# analog-io-breakout.net
KiCad netlist of a schematic drawn in EAGLE
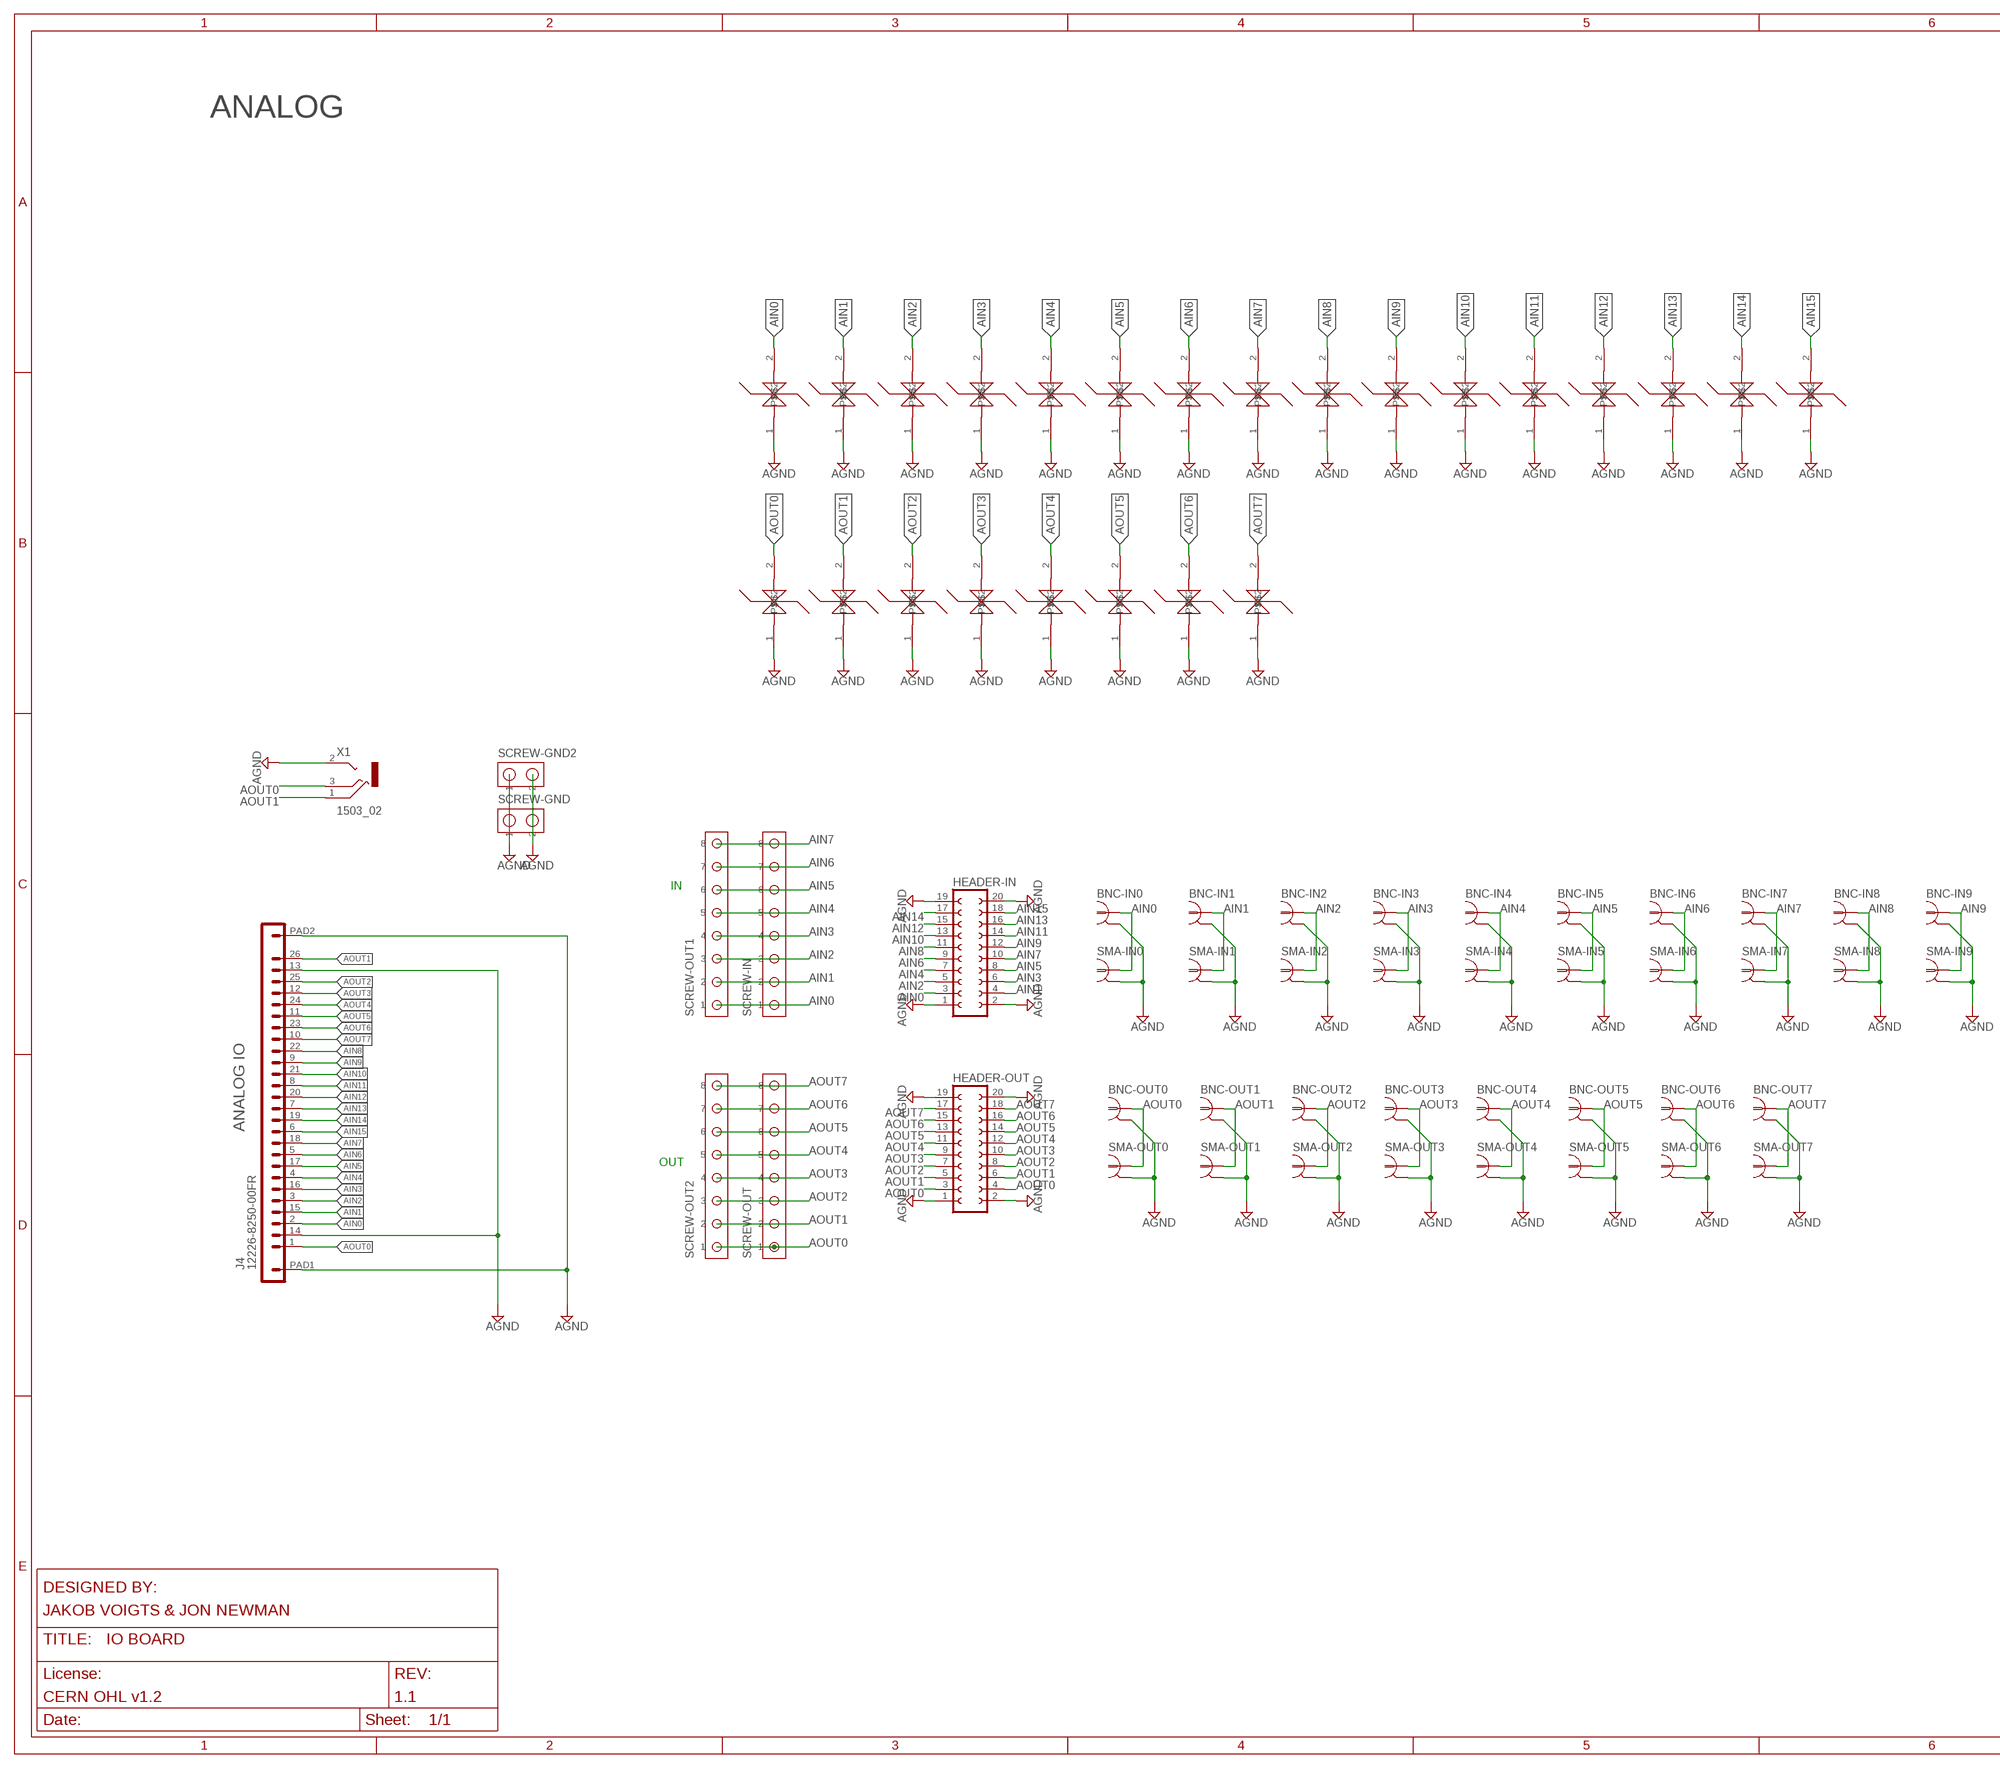
[diagram p0: schematic, sheet 1, part 1 of 2]
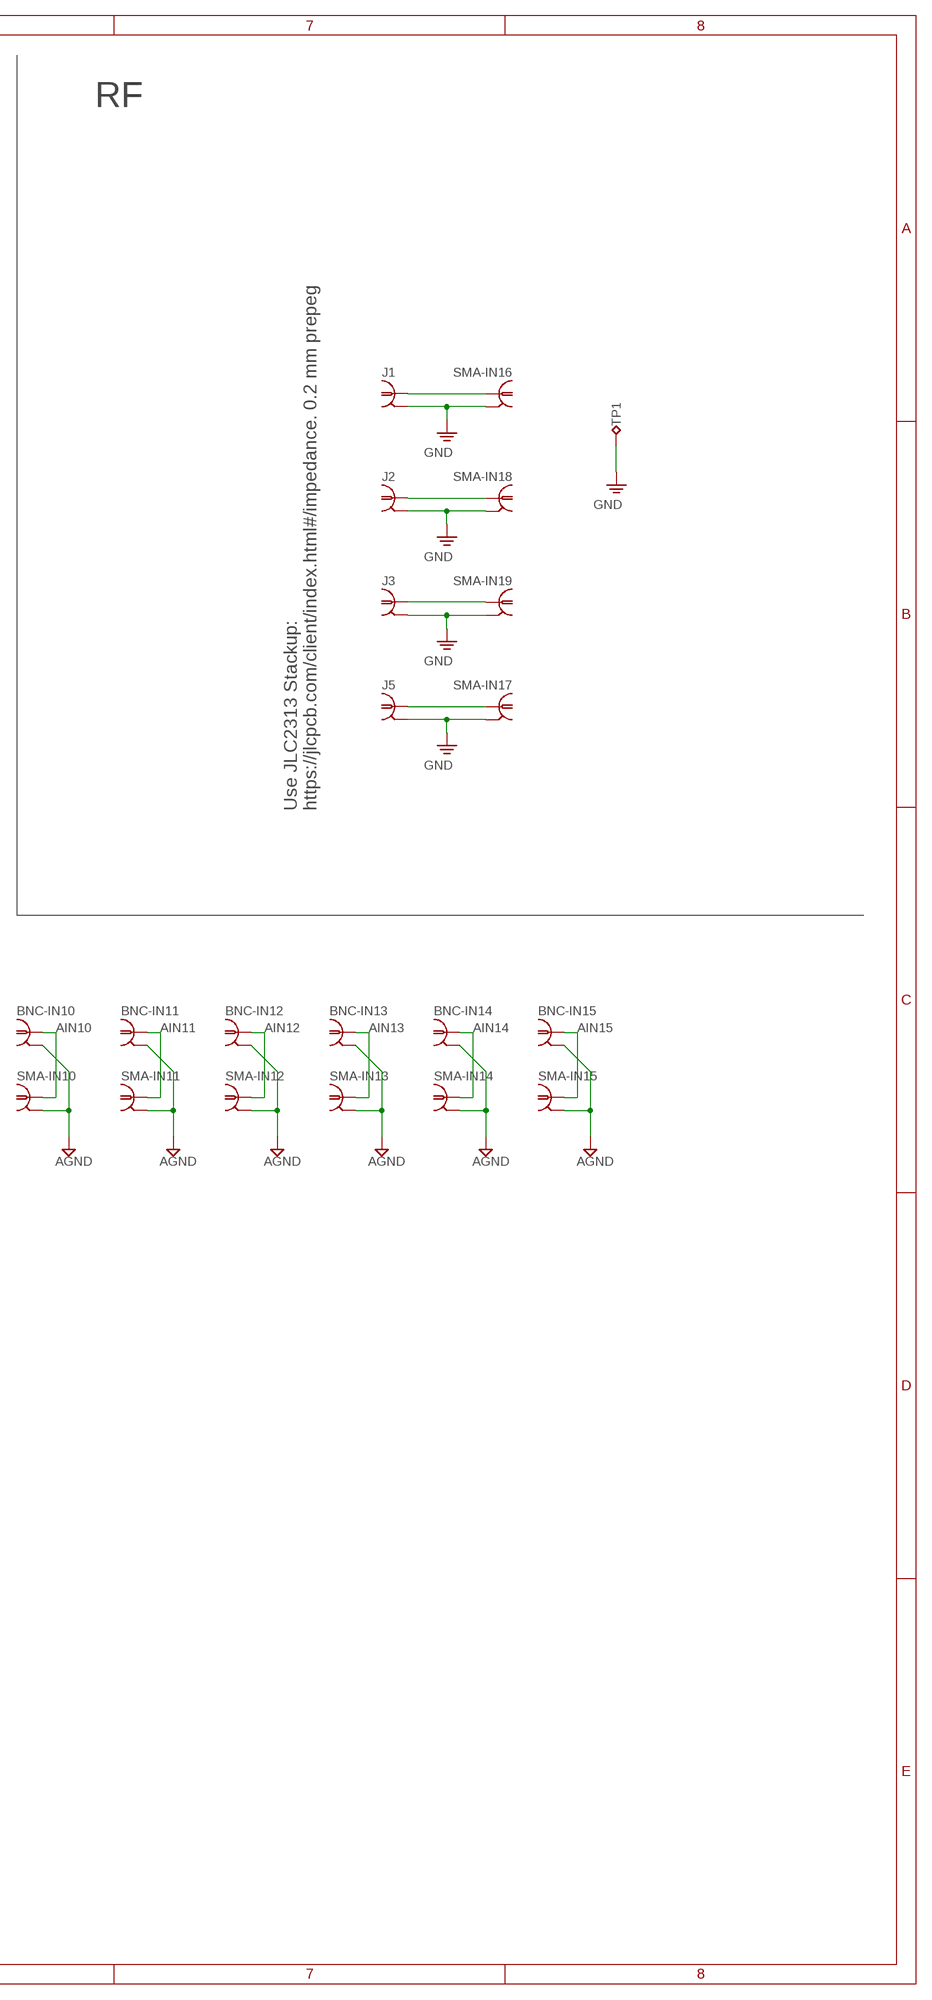
[diagram p1: schematic, sheet 1, part 2 of 2]

(export (version "E")
  (design (tool "Eeschema 10.0.6"))
  (components
    (comp (ref "BNC-IN0")
      (value "COAX_B35N61-LARGE-HOLES")
      (footprint "eagle-import:B35N61_LARGE-HOLES")
      (libsource (lib "eagle-import") (part "COAX_B35N61-LARGE-HOLES"))
    )
    (comp (ref "BNC-IN1")
      (value "COAX_B35N61-LARGE-HOLES")
      (footprint "eagle-import:B35N61_LARGE-HOLES")
      (libsource (lib "eagle-import") (part "COAX_B35N61-LARGE-HOLES"))
    )
    (comp (ref "BNC-IN2")
      (value "COAX_B35N61-LARGE-HOLES")
      (footprint "eagle-import:B35N61_LARGE-HOLES")
      (libsource (lib "eagle-import") (part "COAX_B35N61-LARGE-HOLES"))
    )
    (comp (ref "BNC-IN3")
      (value "COAX_B35N61-LARGE-HOLES")
      (footprint "eagle-import:B35N61_LARGE-HOLES")
      (libsource (lib "eagle-import") (part "COAX_B35N61-LARGE-HOLES"))
    )
    (comp (ref "BNC-IN4")
      (value "COAX_B35N61-LARGE-HOLES")
      (footprint "eagle-import:B35N61_LARGE-HOLES")
      (libsource (lib "eagle-import") (part "COAX_B35N61-LARGE-HOLES"))
    )
    (comp (ref "BNC-IN5")
      (value "COAX_B35N61-LARGE-HOLES")
      (footprint "eagle-import:B35N61_LARGE-HOLES")
      (libsource (lib "eagle-import") (part "COAX_B35N61-LARGE-HOLES"))
    )
    (comp (ref "BNC-IN6")
      (value "COAX_B35N61-LARGE-HOLES")
      (footprint "eagle-import:B35N61_LARGE-HOLES")
      (libsource (lib "eagle-import") (part "COAX_B35N61-LARGE-HOLES"))
    )
    (comp (ref "BNC-IN7")
      (value "COAX_B35N61-LARGE-HOLES")
      (footprint "eagle-import:B35N61_LARGE-HOLES")
      (libsource (lib "eagle-import") (part "COAX_B35N61-LARGE-HOLES"))
    )
    (comp (ref "BNC-IN8")
      (value "COAX_B35N61-LARGE-HOLES")
      (footprint "eagle-import:B35N61_LARGE-HOLES")
      (libsource (lib "eagle-import") (part "COAX_B35N61-LARGE-HOLES"))
    )
    (comp (ref "BNC-IN9")
      (value "COAX_B35N61-LARGE-HOLES")
      (footprint "eagle-import:B35N61_LARGE-HOLES")
      (libsource (lib "eagle-import") (part "COAX_B35N61-LARGE-HOLES"))
    )
    (comp (ref "BNC-IN10")
      (value "COAX_B35N61-LARGE-HOLES")
      (footprint "eagle-import:B35N61_LARGE-HOLES")
      (libsource (lib "eagle-import") (part "COAX_B35N61-LARGE-HOLES"))
    )
    (comp (ref "BNC-IN11")
      (value "COAX_B35N61-LARGE-HOLES")
      (footprint "eagle-import:B35N61_LARGE-HOLES")
      (libsource (lib "eagle-import") (part "COAX_B35N61-LARGE-HOLES"))
    )
    (comp (ref "BNC-IN12")
      (value "COAX_B35N61-LARGE-HOLES")
      (footprint "eagle-import:B35N61_LARGE-HOLES")
      (libsource (lib "eagle-import") (part "COAX_B35N61-LARGE-HOLES"))
    )
    (comp (ref "BNC-IN13")
      (value "COAX_B35N61-LARGE-HOLES")
      (footprint "eagle-import:B35N61_LARGE-HOLES")
      (libsource (lib "eagle-import") (part "COAX_B35N61-LARGE-HOLES"))
    )
    (comp (ref "BNC-IN14")
      (value "COAX_B35N61-LARGE-HOLES")
      (footprint "eagle-import:B35N61_LARGE-HOLES")
      (libsource (lib "eagle-import") (part "COAX_B35N61-LARGE-HOLES"))
    )
    (comp (ref "BNC-IN15")
      (value "COAX_B35N61-LARGE-HOLES")
      (footprint "eagle-import:B35N61_LARGE-HOLES")
      (libsource (lib "eagle-import") (part "COAX_B35N61-LARGE-HOLES"))
    )
    (comp (ref "BNC-OUT0")
      (value "COAX_B35N61-LARGE-HOLES")
      (footprint "eagle-import:B35N61_LARGE-HOLES")
      (libsource (lib "eagle-import") (part "COAX_B35N61-LARGE-HOLES"))
    )
    (comp (ref "BNC-OUT1")
      (value "COAX_B35N61-LARGE-HOLES")
      (footprint "eagle-import:B35N61_LARGE-HOLES")
      (libsource (lib "eagle-import") (part "COAX_B35N61-LARGE-HOLES"))
    )
    (comp (ref "BNC-OUT2")
      (value "COAX_B35N61-LARGE-HOLES")
      (footprint "eagle-import:B35N61_LARGE-HOLES")
      (libsource (lib "eagle-import") (part "COAX_B35N61-LARGE-HOLES"))
    )
    (comp (ref "BNC-OUT3")
      (value "COAX_B35N61-LARGE-HOLES")
      (footprint "eagle-import:B35N61_LARGE-HOLES")
      (libsource (lib "eagle-import") (part "COAX_B35N61-LARGE-HOLES"))
    )
    (comp (ref "BNC-OUT4")
      (value "COAX_B35N61-LARGE-HOLES")
      (footprint "eagle-import:B35N61_LARGE-HOLES")
      (libsource (lib "eagle-import") (part "COAX_B35N61-LARGE-HOLES"))
    )
    (comp (ref "BNC-OUT5")
      (value "COAX_B35N61-LARGE-HOLES")
      (footprint "eagle-import:B35N61_LARGE-HOLES")
      (libsource (lib "eagle-import") (part "COAX_B35N61-LARGE-HOLES"))
    )
    (comp (ref "BNC-OUT6")
      (value "COAX_B35N61-LARGE-HOLES")
      (footprint "eagle-import:B35N61_LARGE-HOLES")
      (libsource (lib "eagle-import") (part "COAX_B35N61-LARGE-HOLES"))
    )
    (comp (ref "BNC-OUT7")
      (value "COAX_B35N61-LARGE-HOLES")
      (footprint "eagle-import:B35N61_LARGE-HOLES")
      (libsource (lib "eagle-import") (part "COAX_B35N61-LARGE-HOLES"))
    )
    (comp (ref "HEADER-IN")
      (value "FE10-2")
      (footprint "eagle-import:FE10-2")
      (libsource (lib "eagle-import") (part "FE10-2"))
    )
    (comp (ref "HEADER-OUT")
      (value "FE10-2")
      (footprint "eagle-import:FE10-2")
      (libsource (lib "eagle-import") (part "FE10-2"))
    )
    (comp (ref "J1")
      (value "COAX_MMCX-RA")
      (footprint "eagle-import:MMCX-J-P-X-RA-SM1")
      (libsource (lib "eagle-import") (part "COAX_MMCX-RA"))
    )
    (comp (ref "J2")
      (value "COAX_MMCX-RA")
      (footprint "eagle-import:MMCX-J-P-X-RA-SM1")
      (libsource (lib "eagle-import") (part "COAX_MMCX-RA"))
    )
    (comp (ref "J3")
      (value "COAX_MMCX-RA")
      (footprint "eagle-import:MMCX-J-P-X-RA-SM1")
      (libsource (lib "eagle-import") (part "COAX_MMCX-RA"))
    )
    (comp (ref "J4")
      (value "12226-8250-00FR")
      (footprint "eagle-import:12226-82X0-00XX")
      (libsource (lib "eagle-import") (part "PINHD-1X26_122"))
    )
    (comp (ref "J5")
      (value "COAX_MMCX-RA")
      (footprint "eagle-import:MMCX-J-P-X-RA-SM1")
      (libsource (lib "eagle-import") (part "COAX_MMCX-RA"))
    )
    (comp (ref "SCREW-GND")
      (value "SCREW2")
      (footprint "eagle-import:SCREW2")
      (libsource (lib "eagle-import") (part "SCREW2"))
    )
    (comp (ref "SCREW-GND2")
      (value "SCREW2")
      (footprint "eagle-import:SCREW2")
      (libsource (lib "eagle-import") (part "SCREW2"))
    )
    (comp (ref "SCREW-IN")
      (value "SCREW8")
      (footprint "eagle-import:SCREW8")
      (libsource (lib "eagle-import") (part "SCREW8"))
    )
    (comp (ref "SCREW-OUT")
      (value "SCREW8")
      (footprint "eagle-import:SCREW8")
      (libsource (lib "eagle-import") (part "SCREW8"))
    )
    (comp (ref "SCREW-OUT1")
      (value "SCREW8")
      (footprint "eagle-import:SCREW8")
      (libsource (lib "eagle-import") (part "SCREW8"))
    )
    (comp (ref "SCREW-OUT2")
      (value "SCREW8")
      (footprint "eagle-import:SCREW8")
      (libsource (lib "eagle-import") (part "SCREW8"))
    )
    (comp (ref "SMA-IN0")
      (value "COAX_SMA-VERT")
      (footprint "eagle-import:SMA_JACK_142-0701-201")
      (libsource (lib "eagle-import") (part "COAX_SMA-VERT"))
    )
    (comp (ref "SMA-IN1")
      (value "COAX_SMA-VERT")
      (footprint "eagle-import:SMA_JACK_142-0701-201")
      (libsource (lib "eagle-import") (part "COAX_SMA-VERT"))
    )
    (comp (ref "SMA-IN2")
      (value "COAX_SMA-VERT")
      (footprint "eagle-import:SMA_JACK_142-0701-201")
      (libsource (lib "eagle-import") (part "COAX_SMA-VERT"))
    )
    (comp (ref "SMA-IN3")
      (value "COAX_SMA-VERT")
      (footprint "eagle-import:SMA_JACK_142-0701-201")
      (libsource (lib "eagle-import") (part "COAX_SMA-VERT"))
    )
    (comp (ref "SMA-IN4")
      (value "COAX_SMA-VERT")
      (footprint "eagle-import:SMA_JACK_142-0701-201")
      (libsource (lib "eagle-import") (part "COAX_SMA-VERT"))
    )
    (comp (ref "SMA-IN5")
      (value "COAX_SMA-VERT")
      (footprint "eagle-import:SMA_JACK_142-0701-201")
      (libsource (lib "eagle-import") (part "COAX_SMA-VERT"))
    )
    (comp (ref "SMA-IN6")
      (value "COAX_SMA-VERT")
      (footprint "eagle-import:SMA_JACK_142-0701-201")
      (libsource (lib "eagle-import") (part "COAX_SMA-VERT"))
    )
    (comp (ref "SMA-IN7")
      (value "COAX_SMA-VERT")
      (footprint "eagle-import:SMA_JACK_142-0701-201")
      (libsource (lib "eagle-import") (part "COAX_SMA-VERT"))
    )
    (comp (ref "SMA-IN8")
      (value "COAX_SMA-VERT")
      (footprint "eagle-import:SMA_JACK_142-0701-201")
      (libsource (lib "eagle-import") (part "COAX_SMA-VERT"))
    )
    (comp (ref "SMA-IN9")
      (value "COAX_SMA-VERT")
      (footprint "eagle-import:SMA_JACK_142-0701-201")
      (libsource (lib "eagle-import") (part "COAX_SMA-VERT"))
    )
    (comp (ref "SMA-IN10")
      (value "COAX_SMA-VERT")
      (footprint "eagle-import:SMA_JACK_142-0701-201")
      (libsource (lib "eagle-import") (part "COAX_SMA-VERT"))
    )
    (comp (ref "SMA-IN11")
      (value "COAX_SMA-VERT")
      (footprint "eagle-import:SMA_JACK_142-0701-201")
      (libsource (lib "eagle-import") (part "COAX_SMA-VERT"))
    )
    (comp (ref "SMA-IN12")
      (value "COAX_SMA-VERT")
      (footprint "eagle-import:SMA_JACK_142-0701-201")
      (libsource (lib "eagle-import") (part "COAX_SMA-VERT"))
    )
    (comp (ref "SMA-IN13")
      (value "COAX_SMA-VERT")
      (footprint "eagle-import:SMA_JACK_142-0701-201")
      (libsource (lib "eagle-import") (part "COAX_SMA-VERT"))
    )
    (comp (ref "SMA-IN14")
      (value "COAX_SMA-VERT")
      (footprint "eagle-import:SMA_JACK_142-0701-201")
      (libsource (lib "eagle-import") (part "COAX_SMA-VERT"))
    )
    (comp (ref "SMA-IN15")
      (value "COAX_SMA-VERT")
      (footprint "eagle-import:SMA_JACK_142-0701-201")
      (libsource (lib "eagle-import") (part "COAX_SMA-VERT"))
    )
    (comp (ref "SMA-IN16")
      (value "COAX_SMA-VERT")
      (footprint "eagle-import:SMA_JACK_142-0701-201")
      (libsource (lib "eagle-import") (part "COAX_SMA-VERT"))
    )
    (comp (ref "SMA-IN17")
      (value "COAX_SMA-VERT")
      (footprint "eagle-import:SMA_JACK_142-0701-201")
      (libsource (lib "eagle-import") (part "COAX_SMA-VERT"))
    )
    (comp (ref "SMA-IN18")
      (value "COAX_SMA-VERT")
      (footprint "eagle-import:SMA_JACK_142-0701-201")
      (libsource (lib "eagle-import") (part "COAX_SMA-VERT"))
    )
    (comp (ref "SMA-IN19")
      (value "COAX_SMA-VERT")
      (footprint "eagle-import:SMA_JACK_142-0701-201")
      (libsource (lib "eagle-import") (part "COAX_SMA-VERT"))
    )
    (comp (ref "SMA-OUT0")
      (value "COAX_SMA-VERT")
      (footprint "eagle-import:SMA_JACK_142-0701-201")
      (libsource (lib "eagle-import") (part "COAX_SMA-VERT"))
    )
    (comp (ref "SMA-OUT1")
      (value "COAX_SMA-VERT")
      (footprint "eagle-import:SMA_JACK_142-0701-201")
      (libsource (lib "eagle-import") (part "COAX_SMA-VERT"))
    )
    (comp (ref "SMA-OUT2")
      (value "COAX_SMA-VERT")
      (footprint "eagle-import:SMA_JACK_142-0701-201")
      (libsource (lib "eagle-import") (part "COAX_SMA-VERT"))
    )
    (comp (ref "SMA-OUT3")
      (value "COAX_SMA-VERT")
      (footprint "eagle-import:SMA_JACK_142-0701-201")
      (libsource (lib "eagle-import") (part "COAX_SMA-VERT"))
    )
    (comp (ref "SMA-OUT4")
      (value "COAX_SMA-VERT")
      (footprint "eagle-import:SMA_JACK_142-0701-201")
      (libsource (lib "eagle-import") (part "COAX_SMA-VERT"))
    )
    (comp (ref "SMA-OUT5")
      (value "COAX_SMA-VERT")
      (footprint "eagle-import:SMA_JACK_142-0701-201")
      (libsource (lib "eagle-import") (part "COAX_SMA-VERT"))
    )
    (comp (ref "SMA-OUT6")
      (value "COAX_SMA-VERT")
      (footprint "eagle-import:SMA_JACK_142-0701-201")
      (libsource (lib "eagle-import") (part "COAX_SMA-VERT"))
    )
    (comp (ref "SMA-OUT7")
      (value "COAX_SMA-VERT")
      (footprint "eagle-import:SMA_JACK_142-0701-201")
      (libsource (lib "eagle-import") (part "COAX_SMA-VERT"))
    )
    (comp (ref "TP1")
      (value "TP_2MM")
      (footprint "eagle-import:TESTPOINT_2MM")
      (libsource (lib "eagle-import") (part "TP_2MM"))
    )
    (comp (ref "U$1")
      (value "DIODE-ESD-BIDIRECTIONALDO-214AA")
      (footprint "eagle-import:DIOC7026X260")
      (libsource (lib "eagle-import") (part "DIODE-ESD-BIDIRECTIONALDO-214AA"))
    )
    (comp (ref "U$2")
      (value "DIODE-ESD-BIDIRECTIONALDO-214AA")
      (footprint "eagle-import:DIOC7026X260")
      (libsource (lib "eagle-import") (part "DIODE-ESD-BIDIRECTIONALDO-214AA"))
    )
    (comp (ref "U$3")
      (value "DIODE-ESD-BIDIRECTIONALDO-214AA")
      (footprint "eagle-import:DIOC7026X260")
      (libsource (lib "eagle-import") (part "DIODE-ESD-BIDIRECTIONALDO-214AA"))
    )
    (comp (ref "U$4")
      (value "DIODE-ESD-BIDIRECTIONALDO-214AA")
      (footprint "eagle-import:DIOC7026X260")
      (libsource (lib "eagle-import") (part "DIODE-ESD-BIDIRECTIONALDO-214AA"))
    )
    (comp (ref "U$5")
      (value "DIODE-ESD-BIDIRECTIONALDO-214AA")
      (footprint "eagle-import:DIOC7026X260")
      (libsource (lib "eagle-import") (part "DIODE-ESD-BIDIRECTIONALDO-214AA"))
    )
    (comp (ref "U$6")
      (value "DIODE-ESD-BIDIRECTIONALDO-214AA")
      (footprint "eagle-import:DIOC7026X260")
      (libsource (lib "eagle-import") (part "DIODE-ESD-BIDIRECTIONALDO-214AA"))
    )
    (comp (ref "U$7")
      (value "DIODE-ESD-BIDIRECTIONALDO-214AA")
      (footprint "eagle-import:DIOC7026X260")
      (libsource (lib "eagle-import") (part "DIODE-ESD-BIDIRECTIONALDO-214AA"))
    )
    (comp (ref "U$8")
      (value "DIODE-ESD-BIDIRECTIONALDO-214AA")
      (footprint "eagle-import:DIOC7026X260")
      (libsource (lib "eagle-import") (part "DIODE-ESD-BIDIRECTIONALDO-214AA"))
    )
    (comp (ref "U$9")
      (value "DIODE-ESD-BIDIRECTIONALDO-214AA")
      (footprint "eagle-import:DIOC7026X260")
      (libsource (lib "eagle-import") (part "DIODE-ESD-BIDIRECTIONALDO-214AA"))
    )
    (comp (ref "U$10")
      (value "DIODE-ESD-BIDIRECTIONALDO-214AA")
      (footprint "eagle-import:DIOC7026X260")
      (libsource (lib "eagle-import") (part "DIODE-ESD-BIDIRECTIONALDO-214AA"))
    )
    (comp (ref "U$11")
      (value "DIODE-ESD-BIDIRECTIONALDO-214AA")
      (footprint "eagle-import:DIOC7026X260")
      (libsource (lib "eagle-import") (part "DIODE-ESD-BIDIRECTIONALDO-214AA"))
    )
    (comp (ref "U$12")
      (value "DIODE-ESD-BIDIRECTIONALDO-214AA")
      (footprint "eagle-import:DIOC7026X260")
      (libsource (lib "eagle-import") (part "DIODE-ESD-BIDIRECTIONALDO-214AA"))
    )
    (comp (ref "U$13")
      (value "DIODE-ESD-BIDIRECTIONALDO-214AA")
      (footprint "eagle-import:DIOC7026X260")
      (libsource (lib "eagle-import") (part "DIODE-ESD-BIDIRECTIONALDO-214AA"))
    )
    (comp (ref "U$14")
      (value "DIODE-ESD-BIDIRECTIONALDO-214AA")
      (footprint "eagle-import:DIOC7026X260")
      (libsource (lib "eagle-import") (part "DIODE-ESD-BIDIRECTIONALDO-214AA"))
    )
    (comp (ref "U$15")
      (value "DIODE-ESD-BIDIRECTIONALDO-214AA")
      (footprint "eagle-import:DIOC7026X260")
      (libsource (lib "eagle-import") (part "DIODE-ESD-BIDIRECTIONALDO-214AA"))
    )
    (comp (ref "U$16")
      (value "DIODE-ESD-BIDIRECTIONALDO-214AA")
      (footprint "eagle-import:DIOC7026X260")
      (libsource (lib "eagle-import") (part "DIODE-ESD-BIDIRECTIONALDO-214AA"))
    )
    (comp (ref "U$17")
      (value "DIODE-ESD-BIDIRECTIONALDO-214AA")
      (footprint "eagle-import:DIOC7026X260")
      (libsource (lib "eagle-import") (part "DIODE-ESD-BIDIRECTIONALDO-214AA"))
    )
    (comp (ref "U$18")
      (value "DIODE-ESD-BIDIRECTIONALDO-214AA")
      (footprint "eagle-import:DIOC7026X260")
      (libsource (lib "eagle-import") (part "DIODE-ESD-BIDIRECTIONALDO-214AA"))
    )
    (comp (ref "U$19")
      (value "DIODE-ESD-BIDIRECTIONALDO-214AA")
      (footprint "eagle-import:DIOC7026X260")
      (libsource (lib "eagle-import") (part "DIODE-ESD-BIDIRECTIONALDO-214AA"))
    )
    (comp (ref "U$20")
      (value "DIODE-ESD-BIDIRECTIONALDO-214AA")
      (footprint "eagle-import:DIOC7026X260")
      (libsource (lib "eagle-import") (part "DIODE-ESD-BIDIRECTIONALDO-214AA"))
    )
    (comp (ref "U$21")
      (value "DIODE-ESD-BIDIRECTIONALDO-214AA")
      (footprint "eagle-import:DIOC7026X260")
      (libsource (lib "eagle-import") (part "DIODE-ESD-BIDIRECTIONALDO-214AA"))
    )
    (comp (ref "U$22")
      (value "DIODE-ESD-BIDIRECTIONALDO-214AA")
      (footprint "eagle-import:DIOC7026X260")
      (libsource (lib "eagle-import") (part "DIODE-ESD-BIDIRECTIONALDO-214AA"))
    )
    (comp (ref "U$23")
      (value "DIODE-ESD-BIDIRECTIONALDO-214AA")
      (footprint "eagle-import:DIOC7026X260")
      (libsource (lib "eagle-import") (part "DIODE-ESD-BIDIRECTIONALDO-214AA"))
    )
    (comp (ref "U$24")
      (value "DIODE-ESD-BIDIRECTIONALDO-214AA")
      (footprint "eagle-import:DIOC7026X260")
      (libsource (lib "eagle-import") (part "DIODE-ESD-BIDIRECTIONALDO-214AA"))
    )
    (comp (ref "X1")
      (value "1503_02")
      (footprint "eagle-import:1503_02")
      (libsource (lib "eagle-import") (part "1503_02"))
    )
  )
  (nets
    (net (code "1") (name "AGND") (class "Default")
      (node (ref "BNC-IN0") (pin "2") (pinfunction "2_2") (pintype "passive"))
      (node (ref "BNC-IN0") (pin "3") (pinfunction "2_3") (pintype "passive"))
      (node (ref "BNC-IN0") (pin "4") (pinfunction "2_4") (pintype "passive"))
      (node (ref "BNC-IN0") (pin "5") (pinfunction "2_5") (pintype "passive"))
      (node (ref "BNC-IN1") (pin "2") (pinfunction "2_2") (pintype "passive"))
      (node (ref "BNC-IN1") (pin "3") (pinfunction "2_3") (pintype "passive"))
      (node (ref "BNC-IN1") (pin "4") (pinfunction "2_4") (pintype "passive"))
      (node (ref "BNC-IN1") (pin "5") (pinfunction "2_5") (pintype "passive"))
      (node (ref "BNC-IN10") (pin "2") (pinfunction "2_2") (pintype "passive"))
      (node (ref "BNC-IN10") (pin "3") (pinfunction "2_3") (pintype "passive"))
      (node (ref "BNC-IN10") (pin "4") (pinfunction "2_4") (pintype "passive"))
      (node (ref "BNC-IN10") (pin "5") (pinfunction "2_5") (pintype "passive"))
      (node (ref "BNC-IN11") (pin "2") (pinfunction "2_2") (pintype "passive"))
      (node (ref "BNC-IN11") (pin "3") (pinfunction "2_3") (pintype "passive"))
      (node (ref "BNC-IN11") (pin "4") (pinfunction "2_4") (pintype "passive"))
      (node (ref "BNC-IN11") (pin "5") (pinfunction "2_5") (pintype "passive"))
      (node (ref "BNC-IN12") (pin "2") (pinfunction "2_2") (pintype "passive"))
      (node (ref "BNC-IN12") (pin "3") (pinfunction "2_3") (pintype "passive"))
      (node (ref "BNC-IN12") (pin "4") (pinfunction "2_4") (pintype "passive"))
      (node (ref "BNC-IN12") (pin "5") (pinfunction "2_5") (pintype "passive"))
      (node (ref "BNC-IN13") (pin "2") (pinfunction "2_2") (pintype "passive"))
      (node (ref "BNC-IN13") (pin "3") (pinfunction "2_3") (pintype "passive"))
      (node (ref "BNC-IN13") (pin "4") (pinfunction "2_4") (pintype "passive"))
      (node (ref "BNC-IN13") (pin "5") (pinfunction "2_5") (pintype "passive"))
      (node (ref "BNC-IN14") (pin "2") (pinfunction "2_2") (pintype "passive"))
      (node (ref "BNC-IN14") (pin "3") (pinfunction "2_3") (pintype "passive"))
      (node (ref "BNC-IN14") (pin "4") (pinfunction "2_4") (pintype "passive"))
      (node (ref "BNC-IN14") (pin "5") (pinfunction "2_5") (pintype "passive"))
      (node (ref "BNC-IN15") (pin "2") (pinfunction "2_2") (pintype "passive"))
      (node (ref "BNC-IN15") (pin "3") (pinfunction "2_3") (pintype "passive"))
      (node (ref "BNC-IN15") (pin "4") (pinfunction "2_4") (pintype "passive"))
      (node (ref "BNC-IN15") (pin "5") (pinfunction "2_5") (pintype "passive"))
      (node (ref "BNC-IN2") (pin "2") (pinfunction "2_2") (pintype "passive"))
      (node (ref "BNC-IN2") (pin "3") (pinfunction "2_3") (pintype "passive"))
      (node (ref "BNC-IN2") (pin "4") (pinfunction "2_4") (pintype "passive"))
      (node (ref "BNC-IN2") (pin "5") (pinfunction "2_5") (pintype "passive"))
      (node (ref "BNC-IN3") (pin "2") (pinfunction "2_2") (pintype "passive"))
      (node (ref "BNC-IN3") (pin "3") (pinfunction "2_3") (pintype "passive"))
      (node (ref "BNC-IN3") (pin "4") (pinfunction "2_4") (pintype "passive"))
      (node (ref "BNC-IN3") (pin "5") (pinfunction "2_5") (pintype "passive"))
      (node (ref "BNC-IN4") (pin "2") (pinfunction "2_2") (pintype "passive"))
      (node (ref "BNC-IN4") (pin "3") (pinfunction "2_3") (pintype "passive"))
      (node (ref "BNC-IN4") (pin "4") (pinfunction "2_4") (pintype "passive"))
      (node (ref "BNC-IN4") (pin "5") (pinfunction "2_5") (pintype "passive"))
      (node (ref "BNC-IN5") (pin "2") (pinfunction "2_2") (pintype "passive"))
      (node (ref "BNC-IN5") (pin "3") (pinfunction "2_3") (pintype "passive"))
      (node (ref "BNC-IN5") (pin "4") (pinfunction "2_4") (pintype "passive"))
      (node (ref "BNC-IN5") (pin "5") (pinfunction "2_5") (pintype "passive"))
      (node (ref "BNC-IN6") (pin "2") (pinfunction "2_2") (pintype "passive"))
      (node (ref "BNC-IN6") (pin "3") (pinfunction "2_3") (pintype "passive"))
      (node (ref "BNC-IN6") (pin "4") (pinfunction "2_4") (pintype "passive"))
      (node (ref "BNC-IN6") (pin "5") (pinfunction "2_5") (pintype "passive"))
      (node (ref "BNC-IN7") (pin "2") (pinfunction "2_2") (pintype "passive"))
      (node (ref "BNC-IN7") (pin "3") (pinfunction "2_3") (pintype "passive"))
      (node (ref "BNC-IN7") (pin "4") (pinfunction "2_4") (pintype "passive"))
      (node (ref "BNC-IN7") (pin "5") (pinfunction "2_5") (pintype "passive"))
      (node (ref "BNC-IN8") (pin "2") (pinfunction "2_2") (pintype "passive"))
      (node (ref "BNC-IN8") (pin "3") (pinfunction "2_3") (pintype "passive"))
      (node (ref "BNC-IN8") (pin "4") (pinfunction "2_4") (pintype "passive"))
      (node (ref "BNC-IN8") (pin "5") (pinfunction "2_5") (pintype "passive"))
      (node (ref "BNC-IN9") (pin "2") (pinfunction "2_2") (pintype "passive"))
      (node (ref "BNC-IN9") (pin "3") (pinfunction "2_3") (pintype "passive"))
      (node (ref "BNC-IN9") (pin "4") (pinfunction "2_4") (pintype "passive"))
      (node (ref "BNC-IN9") (pin "5") (pinfunction "2_5") (pintype "passive"))
      (node (ref "BNC-OUT0") (pin "2") (pinfunction "2_2") (pintype "passive"))
      (node (ref "BNC-OUT0") (pin "3") (pinfunction "2_3") (pintype "passive"))
      (node (ref "BNC-OUT0") (pin "4") (pinfunction "2_4") (pintype "passive"))
      (node (ref "BNC-OUT0") (pin "5") (pinfunction "2_5") (pintype "passive"))
      (node (ref "BNC-OUT1") (pin "2") (pinfunction "2_2") (pintype "passive"))
      (node (ref "BNC-OUT1") (pin "3") (pinfunction "2_3") (pintype "passive"))
      (node (ref "BNC-OUT1") (pin "4") (pinfunction "2_4") (pintype "passive"))
      (node (ref "BNC-OUT1") (pin "5") (pinfunction "2_5") (pintype "passive"))
      (node (ref "BNC-OUT2") (pin "2") (pinfunction "2_2") (pintype "passive"))
      (node (ref "BNC-OUT2") (pin "3") (pinfunction "2_3") (pintype "passive"))
      (node (ref "BNC-OUT2") (pin "4") (pinfunction "2_4") (pintype "passive"))
      (node (ref "BNC-OUT2") (pin "5") (pinfunction "2_5") (pintype "passive"))
      (node (ref "BNC-OUT3") (pin "2") (pinfunction "2_2") (pintype "passive"))
      (node (ref "BNC-OUT3") (pin "3") (pinfunction "2_3") (pintype "passive"))
      (node (ref "BNC-OUT3") (pin "4") (pinfunction "2_4") (pintype "passive"))
      (node (ref "BNC-OUT3") (pin "5") (pinfunction "2_5") (pintype "passive"))
      (node (ref "BNC-OUT4") (pin "2") (pinfunction "2_2") (pintype "passive"))
      (node (ref "BNC-OUT4") (pin "3") (pinfunction "2_3") (pintype "passive"))
      (node (ref "BNC-OUT4") (pin "4") (pinfunction "2_4") (pintype "passive"))
      (node (ref "BNC-OUT4") (pin "5") (pinfunction "2_5") (pintype "passive"))
      (node (ref "BNC-OUT5") (pin "2") (pinfunction "2_2") (pintype "passive"))
      (node (ref "BNC-OUT5") (pin "3") (pinfunction "2_3") (pintype "passive"))
      (node (ref "BNC-OUT5") (pin "4") (pinfunction "2_4") (pintype "passive"))
      (node (ref "BNC-OUT5") (pin "5") (pinfunction "2_5") (pintype "passive"))
      (node (ref "BNC-OUT6") (pin "2") (pinfunction "2_2") (pintype "passive"))
      (node (ref "BNC-OUT6") (pin "3") (pinfunction "2_3") (pintype "passive"))
      (node (ref "BNC-OUT6") (pin "4") (pinfunction "2_4") (pintype "passive"))
      (node (ref "BNC-OUT6") (pin "5") (pinfunction "2_5") (pintype "passive"))
      (node (ref "BNC-OUT7") (pin "2") (pinfunction "2_2") (pintype "passive"))
      (node (ref "BNC-OUT7") (pin "3") (pinfunction "2_3") (pintype "passive"))
      (node (ref "BNC-OUT7") (pin "4") (pinfunction "2_4") (pintype "passive"))
      (node (ref "BNC-OUT7") (pin "5") (pinfunction "2_5") (pintype "passive"))
      (node (ref "HEADER-IN") (pin "1") (pinfunction "1_1") (pintype "passive"))
      (node (ref "HEADER-IN") (pin "19") (pinfunction "19_19") (pintype "passive"))
      (node (ref "HEADER-IN") (pin "2") (pinfunction "2_2") (pintype "passive"))
      (node (ref "HEADER-IN") (pin "20") (pinfunction "20_20") (pintype "passive"))
      (node (ref "HEADER-OUT") (pin "1") (pinfunction "1_1") (pintype "passive"))
      (node (ref "HEADER-OUT") (pin "19") (pinfunction "19_19") (pintype "passive"))
      (node (ref "HEADER-OUT") (pin "2") (pinfunction "2_2") (pintype "passive"))
      (node (ref "HEADER-OUT") (pin "20") (pinfunction "20_20") (pintype "passive"))
      (node (ref "J4") (pin "13") (pinfunction "13_13") (pintype "bidirectional"))
      (node (ref "J4") (pin "14") (pinfunction "14_14") (pintype "bidirectional"))
      (node (ref "J4") (pin "PAD1") (pinfunction "PAD1_PAD1") (pintype "bidirectional"))
      (node (ref "J4") (pin "PAD2") (pinfunction "PAD2_PAD2") (pintype "bidirectional"))
      (node (ref "SCREW-GND") (pin "P$1") (pinfunction "1_P$1") (pintype "passive"))
      (node (ref "SCREW-GND") (pin "P$2") (pinfunction "2_P$2") (pintype "passive"))
      (node (ref "SCREW-GND2") (pin "P$1") (pinfunction "1_P$1") (pintype "passive"))
      (node (ref "SCREW-GND2") (pin "P$2") (pinfunction "2_P$2") (pintype "passive"))
      (node (ref "SMA-IN0") (pin "GND$1") (pinfunction "2_GND$1") (pintype "passive"))
      (node (ref "SMA-IN0") (pin "GND$2") (pinfunction "2_GND$2") (pintype "passive"))
      (node (ref "SMA-IN0") (pin "GND$3") (pinfunction "2_GND$3") (pintype "passive"))
      (node (ref "SMA-IN0") (pin "GND$4") (pinfunction "2_GND$4") (pintype "passive"))
      (node (ref "SMA-IN1") (pin "GND$1") (pinfunction "2_GND$1") (pintype "passive"))
      (node (ref "SMA-IN1") (pin "GND$2") (pinfunction "2_GND$2") (pintype "passive"))
      (node (ref "SMA-IN1") (pin "GND$3") (pinfunction "2_GND$3") (pintype "passive"))
      (node (ref "SMA-IN1") (pin "GND$4") (pinfunction "2_GND$4") (pintype "passive"))
      (node (ref "SMA-IN10") (pin "GND$1") (pinfunction "2_GND$1") (pintype "passive"))
      (node (ref "SMA-IN10") (pin "GND$2") (pinfunction "2_GND$2") (pintype "passive"))
      (node (ref "SMA-IN10") (pin "GND$3") (pinfunction "2_GND$3") (pintype "passive"))
      (node (ref "SMA-IN10") (pin "GND$4") (pinfunction "2_GND$4") (pintype "passive"))
      (node (ref "SMA-IN11") (pin "GND$1") (pinfunction "2_GND$1") (pintype "passive"))
      (node (ref "SMA-IN11") (pin "GND$2") (pinfunction "2_GND$2") (pintype "passive"))
      (node (ref "SMA-IN11") (pin "GND$3") (pinfunction "2_GND$3") (pintype "passive"))
      (node (ref "SMA-IN11") (pin "GND$4") (pinfunction "2_GND$4") (pintype "passive"))
      (node (ref "SMA-IN12") (pin "GND$1") (pinfunction "2_GND$1") (pintype "passive"))
      (node (ref "SMA-IN12") (pin "GND$2") (pinfunction "2_GND$2") (pintype "passive"))
      (node (ref "SMA-IN12") (pin "GND$3") (pinfunction "2_GND$3") (pintype "passive"))
      (node (ref "SMA-IN12") (pin "GND$4") (pinfunction "2_GND$4") (pintype "passive"))
      (node (ref "SMA-IN13") (pin "GND$1") (pinfunction "2_GND$1") (pintype "passive"))
      (node (ref "SMA-IN13") (pin "GND$2") (pinfunction "2_GND$2") (pintype "passive"))
      (node (ref "SMA-IN13") (pin "GND$3") (pinfunction "2_GND$3") (pintype "passive"))
      (node (ref "SMA-IN13") (pin "GND$4") (pinfunction "2_GND$4") (pintype "passive"))
      (node (ref "SMA-IN14") (pin "GND$1") (pinfunction "2_GND$1") (pintype "passive"))
      (node (ref "SMA-IN14") (pin "GND$2") (pinfunction "2_GND$2") (pintype "passive"))
      (node (ref "SMA-IN14") (pin "GND$3") (pinfunction "2_GND$3") (pintype "passive"))
      (node (ref "SMA-IN14") (pin "GND$4") (pinfunction "2_GND$4") (pintype "passive"))
      (node (ref "SMA-IN15") (pin "GND$1") (pinfunction "2_GND$1") (pintype "passive"))
      (node (ref "SMA-IN15") (pin "GND$2") (pinfunction "2_GND$2") (pintype "passive"))
      (node (ref "SMA-IN15") (pin "GND$3") (pinfunction "2_GND$3") (pintype "passive"))
      (node (ref "SMA-IN15") (pin "GND$4") (pinfunction "2_GND$4") (pintype "passive"))
      (node (ref "SMA-IN2") (pin "GND$1") (pinfunction "2_GND$1") (pintype "passive"))
      (node (ref "SMA-IN2") (pin "GND$2") (pinfunction "2_GND$2") (pintype "passive"))
      (node (ref "SMA-IN2") (pin "GND$3") (pinfunction "2_GND$3") (pintype "passive"))
      (node (ref "SMA-IN2") (pin "GND$4") (pinfunction "2_GND$4") (pintype "passive"))
      (node (ref "SMA-IN3") (pin "GND$1") (pinfunction "2_GND$1") (pintype "passive"))
      (node (ref "SMA-IN3") (pin "GND$2") (pinfunction "2_GND$2") (pintype "passive"))
      (node (ref "SMA-IN3") (pin "GND$3") (pinfunction "2_GND$3") (pintype "passive"))
      (node (ref "SMA-IN3") (pin "GND$4") (pinfunction "2_GND$4") (pintype "passive"))
      (node (ref "SMA-IN4") (pin "GND$1") (pinfunction "2_GND$1") (pintype "passive"))
      (node (ref "SMA-IN4") (pin "GND$2") (pinfunction "2_GND$2") (pintype "passive"))
      (node (ref "SMA-IN4") (pin "GND$3") (pinfunction "2_GND$3") (pintype "passive"))
      (node (ref "SMA-IN4") (pin "GND$4") (pinfunction "2_GND$4") (pintype "passive"))
      (node (ref "SMA-IN5") (pin "GND$1") (pinfunction "2_GND$1") (pintype "passive"))
      (node (ref "SMA-IN5") (pin "GND$2") (pinfunction "2_GND$2") (pintype "passive"))
      (node (ref "SMA-IN5") (pin "GND$3") (pinfunction "2_GND$3") (pintype "passive"))
      (node (ref "SMA-IN5") (pin "GND$4") (pinfunction "2_GND$4") (pintype "passive"))
      (node (ref "SMA-IN6") (pin "GND$1") (pinfunction "2_GND$1") (pintype "passive"))
      (node (ref "SMA-IN6") (pin "GND$2") (pinfunction "2_GND$2") (pintype "passive"))
      (node (ref "SMA-IN6") (pin "GND$3") (pinfunction "2_GND$3") (pintype "passive"))
      (node (ref "SMA-IN6") (pin "GND$4") (pinfunction "2_GND$4") (pintype "passive"))
      (node (ref "SMA-IN7") (pin "GND$1") (pinfunction "2_GND$1") (pintype "passive"))
      (node (ref "SMA-IN7") (pin "GND$2") (pinfunction "2_GND$2") (pintype "passive"))
      (node (ref "SMA-IN7") (pin "GND$3") (pinfunction "2_GND$3") (pintype "passive"))
      (node (ref "SMA-IN7") (pin "GND$4") (pinfunction "2_GND$4") (pintype "passive"))
      (node (ref "SMA-IN8") (pin "GND$1") (pinfunction "2_GND$1") (pintype "passive"))
      (node (ref "SMA-IN8") (pin "GND$2") (pinfunction "2_GND$2") (pintype "passive"))
      (node (ref "SMA-IN8") (pin "GND$3") (pinfunction "2_GND$3") (pintype "passive"))
      (node (ref "SMA-IN8") (pin "GND$4") (pinfunction "2_GND$4") (pintype "passive"))
      (node (ref "SMA-IN9") (pin "GND$1") (pinfunction "2_GND$1") (pintype "passive"))
      (node (ref "SMA-IN9") (pin "GND$2") (pinfunction "2_GND$2") (pintype "passive"))
      (node (ref "SMA-IN9") (pin "GND$3") (pinfunction "2_GND$3") (pintype "passive"))
      (node (ref "SMA-IN9") (pin "GND$4") (pinfunction "2_GND$4") (pintype "passive"))
      (node (ref "SMA-OUT0") (pin "GND$1") (pinfunction "2_GND$1") (pintype "passive"))
      (node (ref "SMA-OUT0") (pin "GND$2") (pinfunction "2_GND$2") (pintype "passive"))
      (node (ref "SMA-OUT0") (pin "GND$3") (pinfunction "2_GND$3") (pintype "passive"))
      (node (ref "SMA-OUT0") (pin "GND$4") (pinfunction "2_GND$4") (pintype "passive"))
      (node (ref "SMA-OUT1") (pin "GND$1") (pinfunction "2_GND$1") (pintype "passive"))
      (node (ref "SMA-OUT1") (pin "GND$2") (pinfunction "2_GND$2") (pintype "passive"))
      (node (ref "SMA-OUT1") (pin "GND$3") (pinfunction "2_GND$3") (pintype "passive"))
      (node (ref "SMA-OUT1") (pin "GND$4") (pinfunction "2_GND$4") (pintype "passive"))
      (node (ref "SMA-OUT2") (pin "GND$1") (pinfunction "2_GND$1") (pintype "passive"))
      (node (ref "SMA-OUT2") (pin "GND$2") (pinfunction "2_GND$2") (pintype "passive"))
      (node (ref "SMA-OUT2") (pin "GND$3") (pinfunction "2_GND$3") (pintype "passive"))
      (node (ref "SMA-OUT2") (pin "GND$4") (pinfunction "2_GND$4") (pintype "passive"))
      (node (ref "SMA-OUT3") (pin "GND$1") (pinfunction "2_GND$1") (pintype "passive"))
      (node (ref "SMA-OUT3") (pin "GND$2") (pinfunction "2_GND$2") (pintype "passive"))
      (node (ref "SMA-OUT3") (pin "GND$3") (pinfunction "2_GND$3") (pintype "passive"))
      (node (ref "SMA-OUT3") (pin "GND$4") (pinfunction "2_GND$4") (pintype "passive"))
      (node (ref "SMA-OUT4") (pin "GND$1") (pinfunction "2_GND$1") (pintype "passive"))
      (node (ref "SMA-OUT4") (pin "GND$2") (pinfunction "2_GND$2") (pintype "passive"))
      (node (ref "SMA-OUT4") (pin "GND$3") (pinfunction "2_GND$3") (pintype "passive"))
      (node (ref "SMA-OUT4") (pin "GND$4") (pinfunction "2_GND$4") (pintype "passive"))
      (node (ref "SMA-OUT5") (pin "GND$1") (pinfunction "2_GND$1") (pintype "passive"))
      (node (ref "SMA-OUT5") (pin "GND$2") (pinfunction "2_GND$2") (pintype "passive"))
      (node (ref "SMA-OUT5") (pin "GND$3") (pinfunction "2_GND$3") (pintype "passive"))
      (node (ref "SMA-OUT5") (pin "GND$4") (pinfunction "2_GND$4") (pintype "passive"))
      (node (ref "SMA-OUT6") (pin "GND$1") (pinfunction "2_GND$1") (pintype "passive"))
      (node (ref "SMA-OUT6") (pin "GND$2") (pinfunction "2_GND$2") (pintype "passive"))
      (node (ref "SMA-OUT6") (pin "GND$3") (pinfunction "2_GND$3") (pintype "passive"))
      (node (ref "SMA-OUT6") (pin "GND$4") (pinfunction "2_GND$4") (pintype "passive"))
      (node (ref "SMA-OUT7") (pin "GND$1") (pinfunction "2_GND$1") (pintype "passive"))
      (node (ref "SMA-OUT7") (pin "GND$2") (pinfunction "2_GND$2") (pintype "passive"))
      (node (ref "SMA-OUT7") (pin "GND$3") (pinfunction "2_GND$3") (pintype "passive"))
      (node (ref "SMA-OUT7") (pin "GND$4") (pinfunction "2_GND$4") (pintype "passive"))
      (node (ref "U$1") (pin "1") (pinfunction "P$1_1") (pintype "bidirectional"))
      (node (ref "U$10") (pin "1") (pinfunction "P$1_1") (pintype "bidirectional"))
      (node (ref "U$11") (pin "1") (pinfunction "P$1_1") (pintype "bidirectional"))
      (node (ref "U$12") (pin "1") (pinfunction "P$1_1") (pintype "bidirectional"))
      (node (ref "U$13") (pin "1") (pinfunction "P$1_1") (pintype "bidirectional"))
      (node (ref "U$14") (pin "1") (pinfunction "P$1_1") (pintype "bidirectional"))
      (node (ref "U$15") (pin "1") (pinfunction "P$1_1") (pintype "bidirectional"))
      (node (ref "U$16") (pin "1") (pinfunction "P$1_1") (pintype "bidirectional"))
      (node (ref "U$17") (pin "1") (pinfunction "P$1_1") (pintype "bidirectional"))
      (node (ref "U$18") (pin "1") (pinfunction "P$1_1") (pintype "bidirectional"))
      (node (ref "U$19") (pin "1") (pinfunction "P$1_1") (pintype "bidirectional"))
      (node (ref "U$2") (pin "1") (pinfunction "P$1_1") (pintype "bidirectional"))
      (node (ref "U$20") (pin "1") (pinfunction "P$1_1") (pintype "bidirectional"))
      (node (ref "U$21") (pin "1") (pinfunction "P$1_1") (pintype "bidirectional"))
      (node (ref "U$22") (pin "1") (pinfunction "P$1_1") (pintype "bidirectional"))
      (node (ref "U$23") (pin "1") (pinfunction "P$1_1") (pintype "bidirectional"))
      (node (ref "U$24") (pin "1") (pinfunction "P$1_1") (pintype "bidirectional"))
      (node (ref "U$3") (pin "1") (pinfunction "P$1_1") (pintype "bidirectional"))
      (node (ref "U$4") (pin "1") (pinfunction "P$1_1") (pintype "bidirectional"))
      (node (ref "U$5") (pin "1") (pinfunction "P$1_1") (pintype "bidirectional"))
      (node (ref "U$6") (pin "1") (pinfunction "P$1_1") (pintype "bidirectional"))
      (node (ref "U$7") (pin "1") (pinfunction "P$1_1") (pintype "bidirectional"))
      (node (ref "U$8") (pin "1") (pinfunction "P$1_1") (pintype "bidirectional"))
      (node (ref "U$9") (pin "1") (pinfunction "P$1_1") (pintype "bidirectional"))
      (node (ref "X1") (pin "2") (pinfunction "2_2") (pintype "passive"))
    )
    (net (code "2") (name "AIN0") (class "Default")
      (node (ref "BNC-IN0") (pin "1") (pinfunction "1_1") (pintype "passive"))
      (node (ref "HEADER-IN") (pin "3") (pinfunction "3_3") (pintype "passive"))
      (node (ref "J4") (pin "2") (pinfunction "2_2") (pintype "bidirectional"))
      (node (ref "SCREW-IN") (pin "1") (pinfunction "1_1") (pintype "bidirectional"))
      (node (ref "SCREW-OUT1") (pin "1") (pinfunction "1_1") (pintype "bidirectional"))
      (node (ref "SMA-IN0") (pin "CLK") (pinfunction "1_CLK") (pintype "passive"))
      (node (ref "U$1") (pin "2") (pinfunction "P$2_2") (pintype "bidirectional"))
    )
    (net (code "3") (name "AIN1") (class "Default")
      (node (ref "BNC-IN1") (pin "1") (pinfunction "1_1") (pintype "passive"))
      (node (ref "HEADER-IN") (pin "4") (pinfunction "4_4") (pintype "passive"))
      (node (ref "J4") (pin "15") (pinfunction "15_15") (pintype "bidirectional"))
      (node (ref "SCREW-IN") (pin "2") (pinfunction "2_2") (pintype "bidirectional"))
      (node (ref "SCREW-OUT1") (pin "2") (pinfunction "2_2") (pintype "bidirectional"))
      (node (ref "SMA-IN1") (pin "CLK") (pinfunction "1_CLK") (pintype "passive"))
      (node (ref "U$2") (pin "2") (pinfunction "P$2_2") (pintype "bidirectional"))
    )
    (net (code "4") (name "AIN2") (class "Default")
      (node (ref "BNC-IN2") (pin "1") (pinfunction "1_1") (pintype "passive"))
      (node (ref "HEADER-IN") (pin "5") (pinfunction "5_5") (pintype "passive"))
      (node (ref "J4") (pin "3") (pinfunction "3_3") (pintype "bidirectional"))
      (node (ref "SCREW-IN") (pin "3") (pinfunction "3_3") (pintype "bidirectional"))
      (node (ref "SCREW-OUT1") (pin "3") (pinfunction "3_3") (pintype "bidirectional"))
      (node (ref "SMA-IN2") (pin "CLK") (pinfunction "1_CLK") (pintype "passive"))
      (node (ref "U$3") (pin "2") (pinfunction "P$2_2") (pintype "bidirectional"))
    )
    (net (code "5") (name "AIN3") (class "Default")
      (node (ref "BNC-IN3") (pin "1") (pinfunction "1_1") (pintype "passive"))
      (node (ref "HEADER-IN") (pin "6") (pinfunction "6_6") (pintype "passive"))
      (node (ref "J4") (pin "16") (pinfunction "16_16") (pintype "bidirectional"))
      (node (ref "SCREW-IN") (pin "4") (pinfunction "4_4") (pintype "bidirectional"))
      (node (ref "SCREW-OUT1") (pin "4") (pinfunction "4_4") (pintype "bidirectional"))
      (node (ref "SMA-IN3") (pin "CLK") (pinfunction "1_CLK") (pintype "passive"))
      (node (ref "U$4") (pin "2") (pinfunction "P$2_2") (pintype "bidirectional"))
    )
    (net (code "6") (name "AIN4") (class "Default")
      (node (ref "BNC-IN4") (pin "1") (pinfunction "1_1") (pintype "passive"))
      (node (ref "HEADER-IN") (pin "7") (pinfunction "7_7") (pintype "passive"))
      (node (ref "J4") (pin "4") (pinfunction "4_4") (pintype "bidirectional"))
      (node (ref "SCREW-IN") (pin "5") (pinfunction "5_5") (pintype "bidirectional"))
      (node (ref "SCREW-OUT1") (pin "5") (pinfunction "5_5") (pintype "bidirectional"))
      (node (ref "SMA-IN4") (pin "CLK") (pinfunction "1_CLK") (pintype "passive"))
      (node (ref "U$5") (pin "2") (pinfunction "P$2_2") (pintype "bidirectional"))
    )
    (net (code "7") (name "AIN5") (class "Default")
      (node (ref "BNC-IN5") (pin "1") (pinfunction "1_1") (pintype "passive"))
      (node (ref "HEADER-IN") (pin "8") (pinfunction "8_8") (pintype "passive"))
      (node (ref "J4") (pin "17") (pinfunction "17_17") (pintype "bidirectional"))
      (node (ref "SCREW-IN") (pin "6") (pinfunction "6_6") (pintype "bidirectional"))
      (node (ref "SCREW-OUT1") (pin "6") (pinfunction "6_6") (pintype "bidirectional"))
      (node (ref "SMA-IN5") (pin "CLK") (pinfunction "1_CLK") (pintype "passive"))
      (node (ref "U$6") (pin "2") (pinfunction "P$2_2") (pintype "bidirectional"))
    )
    (net (code "8") (name "AIN6") (class "Default")
      (node (ref "BNC-IN6") (pin "1") (pinfunction "1_1") (pintype "passive"))
      (node (ref "HEADER-IN") (pin "9") (pinfunction "9_9") (pintype "passive"))
      (node (ref "J4") (pin "5") (pinfunction "5_5") (pintype "bidirectional"))
      (node (ref "SCREW-IN") (pin "7") (pinfunction "7_7") (pintype "bidirectional"))
      (node (ref "SCREW-OUT1") (pin "7") (pinfunction "7_7") (pintype "bidirectional"))
      (node (ref "SMA-IN6") (pin "CLK") (pinfunction "1_CLK") (pintype "passive"))
      (node (ref "U$7") (pin "2") (pinfunction "P$2_2") (pintype "bidirectional"))
    )
    (net (code "9") (name "AIN7") (class "Default")
      (node (ref "BNC-IN7") (pin "1") (pinfunction "1_1") (pintype "passive"))
      (node (ref "HEADER-IN") (pin "10") (pinfunction "10_10") (pintype "passive"))
      (node (ref "J4") (pin "18") (pinfunction "18_18") (pintype "bidirectional"))
      (node (ref "SCREW-IN") (pin "8") (pinfunction "8_8") (pintype "bidirectional"))
      (node (ref "SCREW-OUT1") (pin "8") (pinfunction "8_8") (pintype "bidirectional"))
      (node (ref "SMA-IN7") (pin "CLK") (pinfunction "1_CLK") (pintype "passive"))
      (node (ref "U$8") (pin "2") (pinfunction "P$2_2") (pintype "bidirectional"))
    )
    (net (code "10") (name "AIN8") (class "Default")
      (node (ref "BNC-IN8") (pin "1") (pinfunction "1_1") (pintype "passive"))
      (node (ref "HEADER-IN") (pin "11") (pinfunction "11_11") (pintype "passive"))
      (node (ref "J4") (pin "22") (pinfunction "22_22") (pintype "bidirectional"))
      (node (ref "SMA-IN8") (pin "CLK") (pinfunction "1_CLK") (pintype "passive"))
      (node (ref "U$17") (pin "2") (pinfunction "P$2_2") (pintype "bidirectional"))
    )
    (net (code "11") (name "AIN9") (class "Default")
      (node (ref "BNC-IN9") (pin "1") (pinfunction "1_1") (pintype "passive"))
      (node (ref "HEADER-IN") (pin "12") (pinfunction "12_12") (pintype "passive"))
      (node (ref "J4") (pin "9") (pinfunction "9_9") (pintype "bidirectional"))
      (node (ref "SMA-IN9") (pin "CLK") (pinfunction "1_CLK") (pintype "passive"))
      (node (ref "U$18") (pin "2") (pinfunction "P$2_2") (pintype "bidirectional"))
    )
    (net (code "12") (name "AIN10") (class "Default")
      (node (ref "BNC-IN10") (pin "1") (pinfunction "1_1") (pintype "passive"))
      (node (ref "HEADER-IN") (pin "13") (pinfunction "13_13") (pintype "passive"))
      (node (ref "J4") (pin "21") (pinfunction "21_21") (pintype "bidirectional"))
      (node (ref "SMA-IN10") (pin "CLK") (pinfunction "1_CLK") (pintype "passive"))
      (node (ref "U$19") (pin "2") (pinfunction "P$2_2") (pintype "bidirectional"))
    )
    (net (code "13") (name "AIN11") (class "Default")
      (node (ref "BNC-IN11") (pin "1") (pinfunction "1_1") (pintype "passive"))
      (node (ref "HEADER-IN") (pin "14") (pinfunction "14_14") (pintype "passive"))
      (node (ref "J4") (pin "8") (pinfunction "8_8") (pintype "bidirectional"))
      (node (ref "SMA-IN11") (pin "CLK") (pinfunction "1_CLK") (pintype "passive"))
      (node (ref "U$20") (pin "2") (pinfunction "P$2_2") (pintype "bidirectional"))
    )
    (net (code "14") (name "AIN12") (class "Default")
      (node (ref "BNC-IN12") (pin "1") (pinfunction "1_1") (pintype "passive"))
      (node (ref "HEADER-IN") (pin "15") (pinfunction "15_15") (pintype "passive"))
      (node (ref "J4") (pin "20") (pinfunction "20_20") (pintype "bidirectional"))
      (node (ref "SMA-IN12") (pin "CLK") (pinfunction "1_CLK") (pintype "passive"))
      (node (ref "U$21") (pin "2") (pinfunction "P$2_2") (pintype "bidirectional"))
    )
    (net (code "15") (name "AIN13") (class "Default")
      (node (ref "BNC-IN13") (pin "1") (pinfunction "1_1") (pintype "passive"))
      (node (ref "HEADER-IN") (pin "16") (pinfunction "16_16") (pintype "passive"))
      (node (ref "J4") (pin "7") (pinfunction "7_7") (pintype "bidirectional"))
      (node (ref "SMA-IN13") (pin "CLK") (pinfunction "1_CLK") (pintype "passive"))
      (node (ref "U$22") (pin "2") (pinfunction "P$2_2") (pintype "bidirectional"))
    )
    (net (code "16") (name "AIN14") (class "Default")
      (node (ref "BNC-IN14") (pin "1") (pinfunction "1_1") (pintype "passive"))
      (node (ref "HEADER-IN") (pin "17") (pinfunction "17_17") (pintype "passive"))
      (node (ref "J4") (pin "19") (pinfunction "19_19") (pintype "bidirectional"))
      (node (ref "SMA-IN14") (pin "CLK") (pinfunction "1_CLK") (pintype "passive"))
      (node (ref "U$23") (pin "2") (pinfunction "P$2_2") (pintype "bidirectional"))
    )
    (net (code "17") (name "AIN15") (class "Default")
      (node (ref "BNC-IN15") (pin "1") (pinfunction "1_1") (pintype "passive"))
      (node (ref "HEADER-IN") (pin "18") (pinfunction "18_18") (pintype "passive"))
      (node (ref "J4") (pin "6") (pinfunction "6_6") (pintype "bidirectional"))
      (node (ref "SMA-IN15") (pin "CLK") (pinfunction "1_CLK") (pintype "passive"))
      (node (ref "U$24") (pin "2") (pinfunction "P$2_2") (pintype "bidirectional"))
    )
    (net (code "18") (name "AOUT0") (class "Default")
      (node (ref "BNC-OUT0") (pin "1") (pinfunction "1_1") (pintype "passive"))
      (node (ref "HEADER-OUT") (pin "3") (pinfunction "3_3") (pintype "passive"))
      (node (ref "HEADER-OUT") (pin "4") (pinfunction "4_4") (pintype "passive"))
      (node (ref "J4") (pin "1") (pinfunction "1_1") (pintype "bidirectional"))
      (node (ref "SCREW-OUT") (pin "1") (pinfunction "1_1") (pintype "bidirectional"))
      (node (ref "SCREW-OUT2") (pin "1") (pinfunction "1_1") (pintype "bidirectional"))
      (node (ref "SMA-OUT0") (pin "CLK") (pinfunction "1_CLK") (pintype "passive"))
      (node (ref "U$9") (pin "2") (pinfunction "P$2_2") (pintype "bidirectional"))
      (node (ref "X1") (pin "3") (pinfunction "3_3") (pintype "passive"))
    )
    (net (code "19") (name "AOUT1") (class "Default")
      (node (ref "BNC-OUT1") (pin "1") (pinfunction "1_1") (pintype "passive"))
      (node (ref "HEADER-OUT") (pin "5") (pinfunction "5_5") (pintype "passive"))
      (node (ref "HEADER-OUT") (pin "6") (pinfunction "6_6") (pintype "passive"))
      (node (ref "J4") (pin "26") (pinfunction "26_26") (pintype "bidirectional"))
      (node (ref "SCREW-OUT") (pin "2") (pinfunction "2_2") (pintype "bidirectional"))
      (node (ref "SCREW-OUT2") (pin "2") (pinfunction "2_2") (pintype "bidirectional"))
      (node (ref "SMA-OUT1") (pin "CLK") (pinfunction "1_CLK") (pintype "passive"))
      (node (ref "U$10") (pin "2") (pinfunction "P$2_2") (pintype "bidirectional"))
      (node (ref "X1") (pin "1") (pinfunction "1_1") (pintype "passive"))
    )
    (net (code "20") (name "AOUT2") (class "Default")
      (node (ref "BNC-OUT2") (pin "1") (pinfunction "1_1") (pintype "passive"))
      (node (ref "HEADER-OUT") (pin "7") (pinfunction "7_7") (pintype "passive"))
      (node (ref "HEADER-OUT") (pin "8") (pinfunction "8_8") (pintype "passive"))
      (node (ref "J4") (pin "25") (pinfunction "25_25") (pintype "bidirectional"))
      (node (ref "SCREW-OUT") (pin "3") (pinfunction "3_3") (pintype "bidirectional"))
      (node (ref "SCREW-OUT2") (pin "3") (pinfunction "3_3") (pintype "bidirectional"))
      (node (ref "SMA-OUT2") (pin "CLK") (pinfunction "1_CLK") (pintype "passive"))
      (node (ref "U$11") (pin "2") (pinfunction "P$2_2") (pintype "bidirectional"))
    )
    (net (code "21") (name "AOUT3") (class "Default")
      (node (ref "BNC-OUT3") (pin "1") (pinfunction "1_1") (pintype "passive"))
      (node (ref "HEADER-OUT") (pin "10") (pinfunction "10_10") (pintype "passive"))
      (node (ref "HEADER-OUT") (pin "9") (pinfunction "9_9") (pintype "passive"))
      (node (ref "J4") (pin "12") (pinfunction "12_12") (pintype "bidirectional"))
      (node (ref "SCREW-OUT") (pin "4") (pinfunction "4_4") (pintype "bidirectional"))
      (node (ref "SCREW-OUT2") (pin "4") (pinfunction "4_4") (pintype "bidirectional"))
      (node (ref "SMA-OUT3") (pin "CLK") (pinfunction "1_CLK") (pintype "passive"))
      (node (ref "U$12") (pin "2") (pinfunction "P$2_2") (pintype "bidirectional"))
    )
    (net (code "22") (name "AOUT4") (class "Default")
      (node (ref "BNC-OUT4") (pin "1") (pinfunction "1_1") (pintype "passive"))
      (node (ref "HEADER-OUT") (pin "11") (pinfunction "11_11") (pintype "passive"))
      (node (ref "HEADER-OUT") (pin "12") (pinfunction "12_12") (pintype "passive"))
      (node (ref "J4") (pin "24") (pinfunction "24_24") (pintype "bidirectional"))
      (node (ref "SCREW-OUT") (pin "5") (pinfunction "5_5") (pintype "bidirectional"))
      (node (ref "SCREW-OUT2") (pin "5") (pinfunction "5_5") (pintype "bidirectional"))
      (node (ref "SMA-OUT4") (pin "CLK") (pinfunction "1_CLK") (pintype "passive"))
      (node (ref "U$13") (pin "2") (pinfunction "P$2_2") (pintype "bidirectional"))
    )
    (net (code "23") (name "AOUT5") (class "Default")
      (node (ref "BNC-OUT5") (pin "1") (pinfunction "1_1") (pintype "passive"))
      (node (ref "HEADER-OUT") (pin "13") (pinfunction "13_13") (pintype "passive"))
      (node (ref "HEADER-OUT") (pin "14") (pinfunction "14_14") (pintype "passive"))
      (node (ref "J4") (pin "11") (pinfunction "11_11") (pintype "bidirectional"))
      (node (ref "SCREW-OUT") (pin "6") (pinfunction "6_6") (pintype "bidirectional"))
      (node (ref "SCREW-OUT2") (pin "6") (pinfunction "6_6") (pintype "bidirectional"))
      (node (ref "SMA-OUT5") (pin "CLK") (pinfunction "1_CLK") (pintype "passive"))
      (node (ref "U$14") (pin "2") (pinfunction "P$2_2") (pintype "bidirectional"))
    )
    (net (code "24") (name "AOUT6") (class "Default")
      (node (ref "BNC-OUT6") (pin "1") (pinfunction "1_1") (pintype "passive"))
      (node (ref "HEADER-OUT") (pin "15") (pinfunction "15_15") (pintype "passive"))
      (node (ref "HEADER-OUT") (pin "16") (pinfunction "16_16") (pintype "passive"))
      (node (ref "J4") (pin "23") (pinfunction "23_23") (pintype "bidirectional"))
      (node (ref "SCREW-OUT") (pin "7") (pinfunction "7_7") (pintype "bidirectional"))
      (node (ref "SCREW-OUT2") (pin "7") (pinfunction "7_7") (pintype "bidirectional"))
      (node (ref "SMA-OUT6") (pin "CLK") (pinfunction "1_CLK") (pintype "passive"))
      (node (ref "U$15") (pin "2") (pinfunction "P$2_2") (pintype "bidirectional"))
    )
    (net (code "25") (name "AOUT7") (class "Default")
      (node (ref "BNC-OUT7") (pin "1") (pinfunction "1_1") (pintype "passive"))
      (node (ref "HEADER-OUT") (pin "17") (pinfunction "17_17") (pintype "passive"))
      (node (ref "HEADER-OUT") (pin "18") (pinfunction "18_18") (pintype "passive"))
      (node (ref "J4") (pin "10") (pinfunction "10_10") (pintype "bidirectional"))
      (node (ref "SCREW-OUT") (pin "8") (pinfunction "8_8") (pintype "bidirectional"))
      (node (ref "SCREW-OUT2") (pin "8") (pinfunction "8_8") (pintype "bidirectional"))
      (node (ref "SMA-OUT7") (pin "CLK") (pinfunction "1_CLK") (pintype "passive"))
      (node (ref "U$16") (pin "2") (pinfunction "P$2_2") (pintype "bidirectional"))
    )
    (net (code "26") (name "GND") (class "Default")
      (node (ref "J1") (pin "2") (pinfunction "2_2") (pintype "passive"))
      (node (ref "J1") (pin "3") (pinfunction "2_3") (pintype "passive"))
      (node (ref "J1") (pin "4") (pinfunction "2_4") (pintype "passive"))
      (node (ref "J1") (pin "5") (pinfunction "2_5") (pintype "passive"))
      (node (ref "J2") (pin "2") (pinfunction "2_2") (pintype "passive"))
      (node (ref "J2") (pin "3") (pinfunction "2_3") (pintype "passive"))
      (node (ref "J2") (pin "4") (pinfunction "2_4") (pintype "passive"))
      (node (ref "J2") (pin "5") (pinfunction "2_5") (pintype "passive"))
      (node (ref "J3") (pin "2") (pinfunction "2_2") (pintype "passive"))
      (node (ref "J3") (pin "3") (pinfunction "2_3") (pintype "passive"))
      (node (ref "J3") (pin "4") (pinfunction "2_4") (pintype "passive"))
      (node (ref "J3") (pin "5") (pinfunction "2_5") (pintype "passive"))
      (node (ref "J5") (pin "2") (pinfunction "2_2") (pintype "passive"))
      (node (ref "J5") (pin "3") (pinfunction "2_3") (pintype "passive"))
      (node (ref "J5") (pin "4") (pinfunction "2_4") (pintype "passive"))
      (node (ref "J5") (pin "5") (pinfunction "2_5") (pintype "passive"))
      (node (ref "SMA-IN16") (pin "GND$1") (pinfunction "2_GND$1") (pintype "passive"))
      (node (ref "SMA-IN16") (pin "GND$2") (pinfunction "2_GND$2") (pintype "passive"))
      (node (ref "SMA-IN16") (pin "GND$3") (pinfunction "2_GND$3") (pintype "passive"))
      (node (ref "SMA-IN16") (pin "GND$4") (pinfunction "2_GND$4") (pintype "passive"))
      (node (ref "SMA-IN17") (pin "GND$1") (pinfunction "2_GND$1") (pintype "passive"))
      (node (ref "SMA-IN17") (pin "GND$2") (pinfunction "2_GND$2") (pintype "passive"))
      (node (ref "SMA-IN17") (pin "GND$3") (pinfunction "2_GND$3") (pintype "passive"))
      (node (ref "SMA-IN17") (pin "GND$4") (pinfunction "2_GND$4") (pintype "passive"))
      (node (ref "SMA-IN18") (pin "GND$1") (pinfunction "2_GND$1") (pintype "passive"))
      (node (ref "SMA-IN18") (pin "GND$2") (pinfunction "2_GND$2") (pintype "passive"))
      (node (ref "SMA-IN18") (pin "GND$3") (pinfunction "2_GND$3") (pintype "passive"))
      (node (ref "SMA-IN18") (pin "GND$4") (pinfunction "2_GND$4") (pintype "passive"))
      (node (ref "SMA-IN19") (pin "GND$1") (pinfunction "2_GND$1") (pintype "passive"))
      (node (ref "SMA-IN19") (pin "GND$2") (pinfunction "2_GND$2") (pintype "passive"))
      (node (ref "SMA-IN19") (pin "GND$3") (pinfunction "2_GND$3") (pintype "passive"))
      (node (ref "SMA-IN19") (pin "GND$4") (pinfunction "2_GND$4") (pintype "passive"))
      (node (ref "TP1") (pin "1") (pinfunction "TP_1") (pintype "bidirectional"))
    )
    (net (code "27") (name "Net-(SMA-IN16-1)") (class "Default")
      (node (ref "J1") (pin "1") (pinfunction "1_1") (pintype "passive"))
      (node (ref "SMA-IN16") (pin "CLK") (pinfunction "1_CLK") (pintype "passive"))
    )
    (net (code "28") (name "Net-(SMA-IN17-1)") (class "Default")
      (node (ref "J5") (pin "1") (pinfunction "1_1") (pintype "passive"))
      (node (ref "SMA-IN17") (pin "CLK") (pinfunction "1_CLK") (pintype "passive"))
    )
    (net (code "29") (name "Net-(SMA-IN18-1)") (class "Default")
      (node (ref "J2") (pin "1") (pinfunction "1_1") (pintype "passive"))
      (node (ref "SMA-IN18") (pin "CLK") (pinfunction "1_CLK") (pintype "passive"))
    )
    (net (code "30") (name "Net-(SMA-IN19-1)") (class "Default")
      (node (ref "J3") (pin "1") (pinfunction "1_1") (pintype "passive"))
      (node (ref "SMA-IN19") (pin "CLK") (pinfunction "1_CLK") (pintype "passive"))
    )
    (net (code "31") (name "unconnected-(X1-2-Pad2@2)") (class "Default")
      (node (ref "X1") (pin "2@2") (pinfunction "2_2@2") (pintype "passive"))
    )
  )
)
